# 1-stm32.net
KiCad netlist of a schematic drawn in Altium Designer
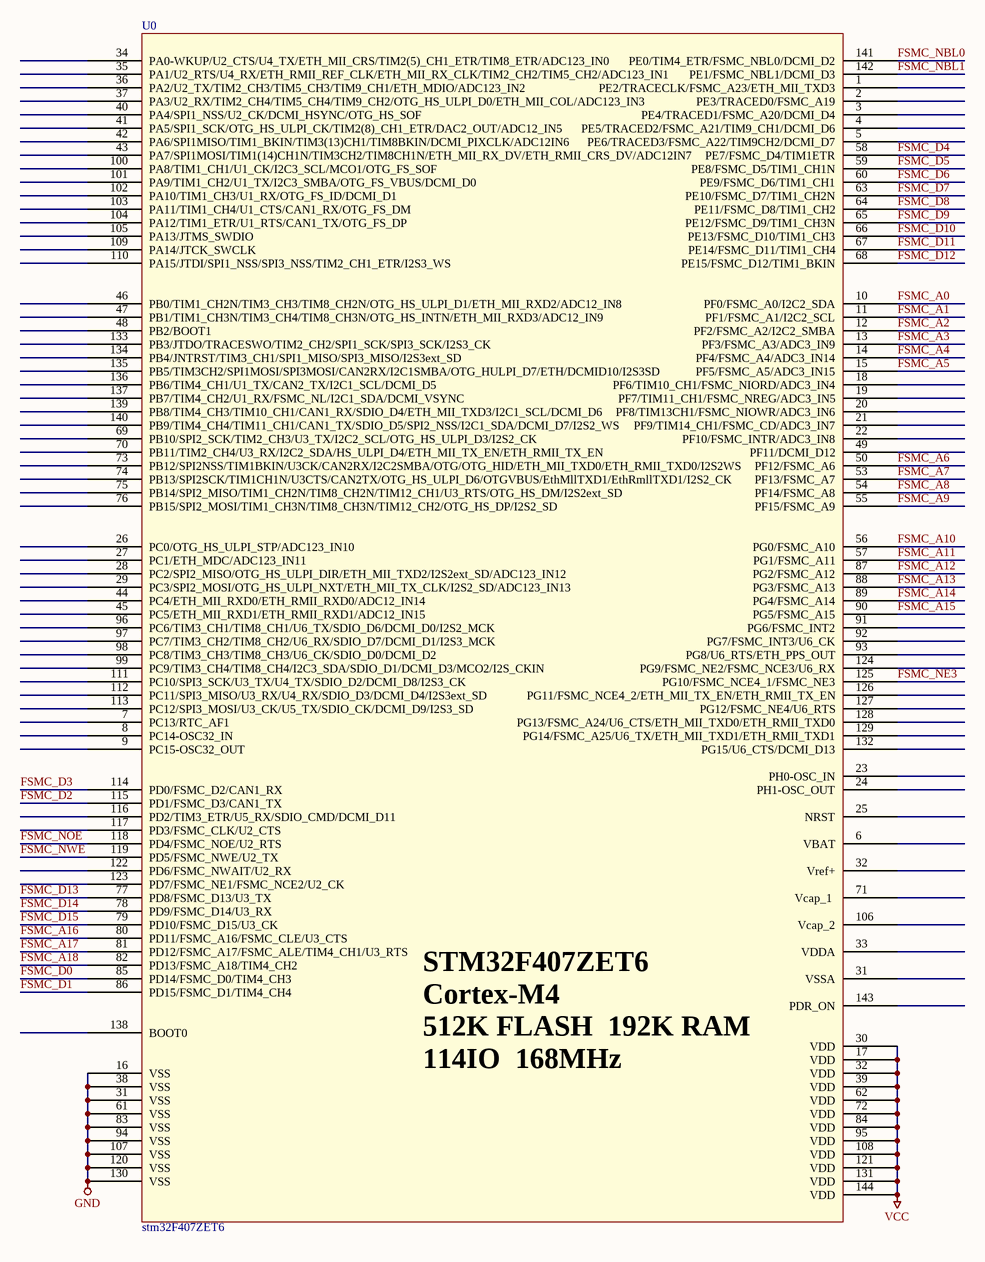
[diagram p0: 1-stm32.SchDoc]

(export (version "E")
  (design (tool "Eeschema 10.0.6"))
  (components
    (comp (ref "U0")
      (value "stm32F407ZET6")
      (footprint "STM-LQFP144_M")
      (libsource (lib "tianxiaohua_Schlib") (part "stm32F407ZET6"))
    )
  )
  (nets
    (net (code "1") (name "/FSMC_A0") (class "Default")
      (node (ref "U0") (pin "10") (pinfunction "PF0/FSMC_A0/I2C2_SDA_10") (pintype "passive"))
    )
    (net (code "2") (name "/FSMC_A1") (class "Default")
      (node (ref "U0") (pin "11") (pinfunction "PF1/FSMC_A1/I2C2_SCL_11") (pintype "passive"))
    )
    (net (code "3") (name "/FSMC_A2") (class "Default")
      (node (ref "U0") (pin "12") (pinfunction "PF2/FSMC_A2/I2C2_SMBA_12") (pintype "passive"))
    )
    (net (code "4") (name "/FSMC_A3") (class "Default")
      (node (ref "U0") (pin "13") (pinfunction "PF3/FSMC_A3/ADC3_IN9_13") (pintype "passive"))
    )
    (net (code "5") (name "/FSMC_A4") (class "Default")
      (node (ref "U0") (pin "14") (pinfunction "PF4/FSMC_A4/ADC3_IN14_14") (pintype "passive"))
    )
    (net (code "6") (name "/FSMC_A5") (class "Default")
      (node (ref "U0") (pin "15") (pinfunction "PF5/FSMC_A5/ADC3_IN15_15") (pintype "passive"))
    )
    (net (code "7") (name "/FSMC_A6") (class "Default")
      (node (ref "U0") (pin "50") (pinfunction "PF12/FSMC_A6_50") (pintype "passive"))
    )
    (net (code "8") (name "/FSMC_A7") (class "Default")
      (node (ref "U0") (pin "53") (pinfunction "PF13/FSMC_A7_53") (pintype "passive"))
    )
    (net (code "9") (name "/FSMC_A8") (class "Default")
      (node (ref "U0") (pin "54") (pinfunction "PF14/FSMC_A8_54") (pintype "passive"))
    )
    (net (code "10") (name "/FSMC_A9") (class "Default")
      (node (ref "U0") (pin "55") (pinfunction "PF15/FSMC_A9_55") (pintype "passive"))
    )
    (net (code "11") (name "/FSMC_A10") (class "Default")
      (node (ref "U0") (pin "56") (pinfunction "PG0/FSMC_A10_56") (pintype "passive"))
    )
    (net (code "12") (name "/FSMC_A11") (class "Default")
      (node (ref "U0") (pin "57") (pinfunction "PG1/FSMC_A11_57") (pintype "passive"))
    )
    (net (code "13") (name "/FSMC_A12") (class "Default")
      (node (ref "U0") (pin "87") (pinfunction "PG2/FSMC_A12_87") (pintype "passive"))
    )
    (net (code "14") (name "/FSMC_A13") (class "Default")
      (node (ref "U0") (pin "88") (pinfunction "PG3/FSMC_A13_88") (pintype "passive"))
    )
    (net (code "15") (name "/FSMC_A14") (class "Default")
      (node (ref "U0") (pin "89") (pinfunction "PG4/FSMC_A14_89") (pintype "passive"))
    )
    (net (code "16") (name "/FSMC_A15") (class "Default")
      (node (ref "U0") (pin "90") (pinfunction "PG5/FSMC_A15_90") (pintype "passive"))
    )
    (net (code "17") (name "/FSMC_A16") (class "Default")
      (node (ref "U0") (pin "80") (pinfunction "PD11/FSMC_A16/FSMC_CLE/U3_CTS_80") (pintype "passive"))
    )
    (net (code "18") (name "/FSMC_A17") (class "Default")
      (node (ref "U0") (pin "81") (pinfunction "PD12/FSMC_A17/FSMC_ALE/TIM4_CH1/U3_RTS_81") (pintype "passive"))
    )
    (net (code "19") (name "/FSMC_A18") (class "Default")
      (node (ref "U0") (pin "82") (pinfunction "PD13/FSMC_A18/TIM4_CH2_82") (pintype "passive"))
    )
    (net (code "20") (name "/FSMC_D0") (class "Default")
      (node (ref "U0") (pin "85") (pinfunction "PD14/FSMC_D0/TIM4_CH3_85") (pintype "passive"))
    )
    (net (code "21") (name "/FSMC_D1") (class "Default")
      (node (ref "U0") (pin "86") (pinfunction "PD15/FSMC_D1/TIM4_CH4_86") (pintype "passive"))
    )
    (net (code "22") (name "/FSMC_D2") (class "Default")
      (node (ref "U0") (pin "115") (pinfunction "PD1/FSMC_D3/CAN1_TX_115") (pintype "passive"))
    )
    (net (code "23") (name "/FSMC_D3") (class "Default")
      (node (ref "U0") (pin "114") (pinfunction "PD0/FSMC_D2/CAN1_RX_114") (pintype "passive"))
    )
    (net (code "24") (name "/FSMC_D4") (class "Default")
      (node (ref "U0") (pin "58") (pinfunction "PE7/FSMC_D4/TIM1ETR_58") (pintype "passive"))
    )
    (net (code "25") (name "/FSMC_D5") (class "Default")
      (node (ref "U0") (pin "59") (pinfunction "PE8/FSMC_D5/TIM1_CH1N_59") (pintype "passive"))
    )
    (net (code "26") (name "/FSMC_D6") (class "Default")
      (node (ref "U0") (pin "60") (pinfunction "PE9/FSMC_D6/TIM1_CH1_60") (pintype "passive"))
    )
    (net (code "27") (name "/FSMC_D7") (class "Default")
      (node (ref "U0") (pin "63") (pinfunction "PE10/FSMC_D7/TIM1_CH2N_63") (pintype "passive"))
    )
    (net (code "28") (name "/FSMC_D8") (class "Default")
      (node (ref "U0") (pin "64") (pinfunction "PE11/FSMC_D8/TIM1_CH2_64") (pintype "passive"))
    )
    (net (code "29") (name "/FSMC_D9") (class "Default")
      (node (ref "U0") (pin "65") (pinfunction "PE12/FSMC_D9/TIM1_CH3N_65") (pintype "passive"))
    )
    (net (code "30") (name "/FSMC_D10") (class "Default")
      (node (ref "U0") (pin "66") (pinfunction "PE13/FSMC_D10/TIM1_CH3_66") (pintype "passive"))
    )
    (net (code "31") (name "/FSMC_D11") (class "Default")
      (node (ref "U0") (pin "67") (pinfunction "PE14/FSMC_D11/TIM1_CH4_67") (pintype "passive"))
    )
    (net (code "32") (name "/FSMC_D12") (class "Default")
      (node (ref "U0") (pin "68") (pinfunction "PE15/FSMC_D12/TIM1_BKIN_68") (pintype "passive"))
    )
    (net (code "33") (name "/FSMC_D13") (class "Default")
      (node (ref "U0") (pin "77") (pinfunction "PD8/FSMC_D13/U3_TX_77") (pintype "passive"))
    )
    (net (code "34") (name "/FSMC_D14") (class "Default")
      (node (ref "U0") (pin "78") (pinfunction "PD9/FSMC_D14/U3_RX_78") (pintype "passive"))
    )
    (net (code "35") (name "/FSMC_D15") (class "Default")
      (node (ref "U0") (pin "79") (pinfunction "PD10/FSMC_D15/U3_CK_79") (pintype "passive"))
    )
    (net (code "36") (name "/FSMC_NBL0") (class "Default")
      (node (ref "U0") (pin "141") (pinfunction "PE0/TIM4_ETR/FSMC_NBL0/DCMI_D2_141") (pintype "passive"))
    )
    (net (code "37") (name "/FSMC_NBL1") (class "Default")
      (node (ref "U0") (pin "142") (pinfunction "PE1/FSMC_NBL1/DCMI_D3_142") (pintype "passive"))
    )
    (net (code "38") (name "/FSMC_NE3") (class "Default")
      (node (ref "U0") (pin "125") (pinfunction "PG10/FSMC_NCE4_1/FSMC_NE3_125") (pintype "passive"))
    )
    (net (code "39") (name "/FSMC_NOE") (class "Default")
      (node (ref "U0") (pin "118") (pinfunction "PD4/FSMC_NOE/U2_RTS_118") (pintype "passive"))
    )
    (net (code "40") (name "/FSMC_NWE") (class "Default")
      (node (ref "U0") (pin "119") (pinfunction "PD5/FSMC_NWE/U2_TX_119") (pintype "passive"))
    )
    (net (code "41") (name "GND") (class "Default")
      (node (ref "U0") (pin "107") (pinfunction "VSS_107") (pintype "passive"))
      (node (ref "U0") (pin "120") (pinfunction "VSS_120") (pintype "passive"))
      (node (ref "U0") (pin "130") (pinfunction "VSS_130") (pintype "passive"))
      (node (ref "U0") (pin "16") (pinfunction "VSS_16") (pintype "passive"))
      (node (ref "U0") (pin "31") (pinfunction "VSS_31") (pintype "passive"))
      (node (ref "U0") (pin "38") (pinfunction "VSS_38") (pintype "passive"))
      (node (ref "U0") (pin "61") (pinfunction "VSS_61") (pintype "passive"))
      (node (ref "U0") (pin "83") (pinfunction "VSS_83") (pintype "passive"))
      (node (ref "U0") (pin "94") (pinfunction "VSS_94") (pintype "passive"))
    )
    (net (code "42") (name "VCC") (class "Default")
      (node (ref "U0") (pin "108") (pinfunction "VDD_108") (pintype "passive"))
      (node (ref "U0") (pin "121") (pinfunction "VDD_121") (pintype "passive"))
      (node (ref "U0") (pin "131") (pinfunction "VDD_131") (pintype "passive"))
      (node (ref "U0") (pin "144") (pinfunction "VDD_144") (pintype "passive"))
      (node (ref "U0") (pin "17") (pinfunction "VDD_17") (pintype "passive"))
      (node (ref "U0") (pin "30") (pinfunction "VDD_30") (pintype "passive"))
      (node (ref "U0") (pin "32") (pinfunction "VDD_32") (pintype "passive"))
      (node (ref "U0") (pin "39") (pinfunction "VDD_39") (pintype "passive"))
      (node (ref "U0") (pin "62") (pinfunction "VDD_62") (pintype "passive"))
      (node (ref "U0") (pin "72") (pinfunction "VDD_72") (pintype "passive"))
      (node (ref "U0") (pin "84") (pinfunction "VDD_84") (pintype "passive"))
      (node (ref "U0") (pin "95") (pinfunction "VDD_95") (pintype "passive"))
    )
    (net (code "43") (name "unconnected-(U0-BOOT0-Pad138)") (class "Default")
      (node (ref "U0") (pin "138") (pinfunction "BOOT0_138") (pintype "passive"))
    )
    (net (code "44") (name "unconnected-(U0-NRST-Pad25)") (class "Default")
      (node (ref "U0") (pin "25") (pinfunction "NRST_25") (pintype "passive"))
    )
    (net (code "45") (name "unconnected-(U0-PA0-WKUP{slash}U2_CTS{slash}U4_TX{slash}ETH_MII_CRS{slash}TIM2(5)_CH1_ETR{slash}TIM8_ETR{slash}ADC123_IN0-Pad34)") (class "Default")
      (node (ref "U0") (pin "34") (pinfunction "PA0-WKUP/U2_CTS/U4_TX/ETH_MII_CRS/TIM2(5)_CH1_ETR/TIM8_ETR/ADC123_IN0_34") (pintype "passive"))
    )
    (net (code "46") (name "unconnected-(U0-PA1{slash}U2_RTS{slash}U4_RX{slash}ETH_RMII_REF_CLK{slash}ETH_MII_RX_CLK{slash}TIM2_CH2{slash}TIM5_CH2{slash}ADC123_IN1-Pad35)") (class "Default")
      (node (ref "U0") (pin "35") (pinfunction "PA1/U2_RTS/U4_RX/ETH_RMII_REF_CLK/ETH_MII_RX_CLK/TIM2_CH2/TIM5_CH2/ADC123_IN1_35") (pintype "passive"))
    )
    (net (code "47") (name "unconnected-(U0-PA2{slash}U2_TX{slash}TIM2_CH3{slash}TIM5_CH3{slash}TIM9_CH1{slash}ETH_MDIO{slash}ADC123_IN2-Pad36)") (class "Default")
      (node (ref "U0") (pin "36") (pinfunction "PA2/U2_TX/TIM2_CH3/TIM5_CH3/TIM9_CH1/ETH_MDIO/ADC123_IN2_36") (pintype "passive"))
    )
    (net (code "48") (name "unconnected-(U0-PA3{slash}U2_RX{slash}TIM2_CH4{slash}TIM5_CH4{slash}TIM9_CH2{slash}OTG_HS_ULPI_D0{slash}ETH_MII_COL{slash}ADC123_IN3-Pad37)") (class "Default")
      (node (ref "U0") (pin "37") (pinfunction "PA3/U2_RX/TIM2_CH4/TIM5_CH4/TIM9_CH2/OTG_HS_ULPI_D0/ETH_MII_COL/ADC123_IN3_37") (pintype "passive"))
    )
    (net (code "49") (name "unconnected-(U0-PA4{slash}SPI1_NSS{slash}U2_CK{slash}DCMI_HSYNC{slash}OTG_HS_SOF-Pad40)") (class "Default")
      (node (ref "U0") (pin "40") (pinfunction "PA4/SPI1_NSS/U2_CK/DCMI_HSYNC/OTG_HS_SOF_40") (pintype "passive"))
    )
    (net (code "50") (name "unconnected-(U0-PA5{slash}SPI1_SCK{slash}OTG_HS_ULPI_CK{slash}TIM2(8)_CH1_ETR{slash}DAC2_OUT{slash}ADC12_IN5-Pad41)") (class "Default")
      (node (ref "U0") (pin "41") (pinfunction "PA5/SPI1_SCK/OTG_HS_ULPI_CK/TIM2(8)_CH1_ETR/DAC2_OUT/ADC12_IN5_41") (pintype "passive"))
    )
    (net (code "51") (name "unconnected-(U0-PA6{slash}SPI1MISO{slash}TIM1_BKIN{slash}TIM3(13)CH1{slash}TIM8BKIN{slash}DCMI_PIXCLK{slash}ADC12IN6-Pad42)") (class "Default")
      (node (ref "U0") (pin "42") (pinfunction "PA6/SPI1MISO/TIM1_BKIN/TIM3(13)CH1/TIM8BKIN/DCMI_PIXCLK/ADC12IN6_42") (pintype "passive"))
    )
    (net (code "52") (name "unconnected-(U0-PA7{slash}SPI1MOSI{slash}TIM1(14)CH1N{slash}TIM3CH2{slash}TIM8CH1N{slash}ETH_MII_RX_DV{slash}ETH_RMII_CRS_DV{slash}ADC12IN7-Pad43)") (class "Default")
      (node (ref "U0") (pin "43") (pinfunction "PA7/SPI1MOSI/TIM1(14)CH1N/TIM3CH2/TIM8CH1N/ETH_MII_RX_DV/ETH_RMII_CRS_DV/ADC12IN7_43") (pintype "passive"))
    )
    (net (code "53") (name "unconnected-(U0-PA8{slash}TIM1_CH1{slash}U1_CK{slash}I2C3_SCL{slash}MCO1{slash}OTG_FS_SOF-Pad100)") (class "Default")
      (node (ref "U0") (pin "100") (pinfunction "PA8/TIM1_CH1/U1_CK/I2C3_SCL/MCO1/OTG_FS_SOF_100") (pintype "passive"))
    )
    (net (code "54") (name "unconnected-(U0-PA9{slash}TIM1_CH2{slash}U1_TX{slash}I2C3_SMBA{slash}OTG_FS_VBUS{slash}DCMI_D0-Pad101)") (class "Default")
      (node (ref "U0") (pin "101") (pinfunction "PA9/TIM1_CH2/U1_TX/I2C3_SMBA/OTG_FS_VBUS/DCMI_D0_101") (pintype "passive"))
    )
    (net (code "55") (name "unconnected-(U0-PA10{slash}TIM1_CH3{slash}U1_RX{slash}OTG_FS_ID{slash}DCMI_D1-Pad102)") (class "Default")
      (node (ref "U0") (pin "102") (pinfunction "PA10/TIM1_CH3/U1_RX/OTG_FS_ID/DCMI_D1_102") (pintype "passive"))
    )
    (net (code "56") (name "unconnected-(U0-PA11{slash}TIM1_CH4{slash}U1_CTS{slash}CAN1_RX{slash}OTG_FS_DM-Pad103)") (class "Default")
      (node (ref "U0") (pin "103") (pinfunction "PA11/TIM1_CH4/U1_CTS/CAN1_RX/OTG_FS_DM_103") (pintype "passive"))
    )
    (net (code "57") (name "unconnected-(U0-PA12{slash}TIM1_ETR{slash}U1_RTS{slash}CAN1_TX{slash}OTG_FS_DP-Pad104)") (class "Default")
      (node (ref "U0") (pin "104") (pinfunction "PA12/TIM1_ETR/U1_RTS/CAN1_TX/OTG_FS_DP_104") (pintype "passive"))
    )
    (net (code "58") (name "unconnected-(U0-PA13{slash}JTMS_SWDIO-Pad105)") (class "Default")
      (node (ref "U0") (pin "105") (pinfunction "PA13/JTMS_SWDIO_105") (pintype "passive"))
    )
    (net (code "59") (name "unconnected-(U0-PA14{slash}JTCK_SWCLK-Pad109)") (class "Default")
      (node (ref "U0") (pin "109") (pinfunction "PA14/JTCK_SWCLK_109") (pintype "passive"))
    )
    (net (code "60") (name "unconnected-(U0-PA15{slash}JTDI{slash}SPI1_NSS{slash}SPI3_NSS{slash}TIM2_CH1_ETR{slash}I2S3_WS-Pad110)") (class "Default")
      (node (ref "U0") (pin "110") (pinfunction "PA15/JTDI/SPI1_NSS/SPI3_NSS/TIM2_CH1_ETR/I2S3_WS_110") (pintype "passive"))
    )
    (net (code "61") (name "unconnected-(U0-PB0{slash}TIM1_CH2N{slash}TIM3_CH3{slash}TIM8_CH2N{slash}OTG_HS_ULPI_D1{slash}ETH_MII_RXD2{slash}ADC12_IN8-Pad46)") (class "Default")
      (node (ref "U0") (pin "46") (pinfunction "PB0/TIM1_CH2N/TIM3_CH3/TIM8_CH2N/OTG_HS_ULPI_D1/ETH_MII_RXD2/ADC12_IN8_46") (pintype "passive"))
    )
    (net (code "62") (name "unconnected-(U0-PB1{slash}TIM1_CH3N{slash}TIM3_CH4{slash}TIM8_CH3N{slash}OTG_HS_INTN{slash}ETH_MII_RXD3{slash}ADC12_IN9-Pad47)") (class "Default")
      (node (ref "U0") (pin "47") (pinfunction "PB1/TIM1_CH3N/TIM3_CH4/TIM8_CH3N/OTG_HS_INTN/ETH_MII_RXD3/ADC12_IN9_47") (pintype "passive"))
    )
    (net (code "63") (name "unconnected-(U0-PB2{slash}BOOT1-Pad48)") (class "Default")
      (node (ref "U0") (pin "48") (pinfunction "PB2/BOOT1_48") (pintype "passive"))
    )
    (net (code "64") (name "unconnected-(U0-PB3{slash}JTDO{slash}TRACESWO{slash}TIM2_CH2{slash}SPI1_SCK{slash}SPI3_SCK{slash}I2S3_CK-Pad133)") (class "Default")
      (node (ref "U0") (pin "133") (pinfunction "PB3/JTDO/TRACESWO/TIM2_CH2/SPI1_SCK/SPI3_SCK/I2S3_CK_133") (pintype "passive"))
    )
    (net (code "65") (name "unconnected-(U0-PB4{slash}JNTRST{slash}TIM3_CH1{slash}SPI1_MISO{slash}SPI3_MISO{slash}I2S3ext_SD-Pad134)") (class "Default")
      (node (ref "U0") (pin "134") (pinfunction "PB4/JNTRST/TIM3_CH1/SPI1_MISO/SPI3_MISO/I2S3ext_SD_134") (pintype "passive"))
    )
    (net (code "66") (name "unconnected-(U0-PB5{slash}TIM3CH2{slash}SPI1MOSI{slash}SPI3MOSI{slash}CAN2RX{slash}I2C1SMBA{slash}OTG_HULPI_D7{slash}ETH{slash}DCMID10{slash}I2S3SD-Pad135)") (class "Default")
      (node (ref "U0") (pin "135") (pinfunction "PB5/TIM3CH2/SPI1MOSI/SPI3MOSI/CAN2RX/I2C1SMBA/OTG_HULPI_D7/ETH/DCMID10/I2S3SD_135") (pintype "passive"))
    )
    (net (code "67") (name "unconnected-(U0-PB6{slash}TIM4_CH1{slash}U1_TX{slash}CAN2_TX{slash}I2C1_SCL{slash}DCMI_D5-Pad136)") (class "Default")
      (node (ref "U0") (pin "136") (pinfunction "PB6/TIM4_CH1/U1_TX/CAN2_TX/I2C1_SCL/DCMI_D5_136") (pintype "passive"))
    )
    (net (code "68") (name "unconnected-(U0-PB7{slash}TIM4_CH2{slash}U1_RX{slash}FSMC_NL{slash}I2C1_SDA{slash}DCMI_VSYNC-Pad137)") (class "Default")
      (node (ref "U0") (pin "137") (pinfunction "PB7/TIM4_CH2/U1_RX/FSMC_NL/I2C1_SDA/DCMI_VSYNC_137") (pintype "passive"))
    )
    (net (code "69") (name "unconnected-(U0-PB8{slash}TIM4_CH3{slash}TIM10_CH1{slash}CAN1_RX{slash}SDIO_D4{slash}ETH_MII_TXD3{slash}I2C1_SCL{slash}DCMI_D6-Pad139)") (class "Default")
      (node (ref "U0") (pin "139") (pinfunction "PB8/TIM4_CH3/TIM10_CH1/CAN1_RX/SDIO_D4/ETH_MII_TXD3/I2C1_SCL/DCMI_D6_139") (pintype "passive"))
    )
    (net (code "70") (name "unconnected-(U0-PB9{slash}TIM4_CH4{slash}TIM11_CH1{slash}CAN1_TX{slash}SDIO_D5{slash}SPI2_NSS{slash}I2C1_SDA{slash}DCMI_D7{slash}I2S2_WS-Pad140)") (class "Default")
      (node (ref "U0") (pin "140") (pinfunction "PB9/TIM4_CH4/TIM11_CH1/CAN1_TX/SDIO_D5/SPI2_NSS/I2C1_SDA/DCMI_D7/I2S2_WS_140") (pintype "passive"))
    )
    (net (code "71") (name "unconnected-(U0-PB10{slash}SPI2_SCK{slash}TIM2_CH3{slash}U3_TX{slash}I2C2_SCL{slash}OTG_HS_ULPI_D3{slash}I2S2_CK-Pad69)") (class "Default")
      (node (ref "U0") (pin "69") (pinfunction "PB10/SPI2_SCK/TIM2_CH3/U3_TX/I2C2_SCL/OTG_HS_ULPI_D3/I2S2_CK_69") (pintype "passive"))
    )
    (net (code "72") (name "unconnected-(U0-PB11{slash}TIM2_CH4{slash}U3_RX{slash}I2C2_SDA{slash}HS_ULPI_D4{slash}ETH_MII_TX_EN{slash}ETH_RMII_TX_EN-Pad70)") (class "Default")
      (node (ref "U0") (pin "70") (pinfunction "PB11/TIM2_CH4/U3_RX/I2C2_SDA/HS_ULPI_D4/ETH_MII_TX_EN/ETH_RMII_TX_EN_70") (pintype "passive"))
    )
    (net (code "73") (name "unconnected-(U0-PB12{slash}SPI2NSS{slash}TIM1BKIN{slash}U3CK{slash}CAN2RX{slash}I2C2SMBA{slash}OTG{slash}OTG_HID{slash}ETH_MII_TXD0{slash}ETH_RMII_TXD0{slash}I2S2WS-Pad73)") (class "Default")
      (node (ref "U0") (pin "73") (pinfunction "PB12/SPI2NSS/TIM1BKIN/U3CK/CAN2RX/I2C2SMBA/OTG/OTG_HID/ETH_MII_TXD0/ETH_RMII_TXD0/I2S2WS_73") (pintype "passive"))
    )
    (net (code "74") (name "unconnected-(U0-PB13{slash}SPI2SCK{slash}TIM1CH1N{slash}U3CTS{slash}CAN2TX{slash}OTG_HS_ULPI_D6{slash}OTGVBUS{slash}EthMllTXD1{slash}EthRmllTXD1{slash}I2S2_CK-Pad74)") (class "Default")
      (node (ref "U0") (pin "74") (pinfunction "PB13/SPI2SCK/TIM1CH1N/U3CTS/CAN2TX/OTG_HS_ULPI_D6/OTGVBUS/EthMllTXD1/EthRmllTXD1/I2S2_CK_74") (pintype "passive"))
    )
    (net (code "75") (name "unconnected-(U0-PB14{slash}SPI2_MISO{slash}TIM1_CH2N{slash}TIM8_CH2N{slash}TIM12_CH1{slash}U3_RTS{slash}OTG_HS_DM{slash}I2S2ext_SD-Pad75)") (class "Default")
      (node (ref "U0") (pin "75") (pinfunction "PB14/SPI2_MISO/TIM1_CH2N/TIM8_CH2N/TIM12_CH1/U3_RTS/OTG_HS_DM/I2S2ext_SD_75") (pintype "passive"))
    )
    (net (code "76") (name "unconnected-(U0-PB15{slash}SPI2_MOSI{slash}TIM1_CH3N{slash}TIM8_CH3N{slash}TIM12_CH2{slash}OTG_HS_DP{slash}I2S2_SD-Pad76)") (class "Default")
      (node (ref "U0") (pin "76") (pinfunction "PB15/SPI2_MOSI/TIM1_CH3N/TIM8_CH3N/TIM12_CH2/OTG_HS_DP/I2S2_SD_76") (pintype "passive"))
    )
    (net (code "77") (name "unconnected-(U0-PC0{slash}OTG_HS_ULPI_STP{slash}ADC123_IN10-Pad26)") (class "Default")
      (node (ref "U0") (pin "26") (pinfunction "PC0/OTG_HS_ULPI_STP/ADC123_IN10_26") (pintype "passive"))
    )
    (net (code "78") (name "unconnected-(U0-PC1{slash}ETH_MDC{slash}ADC123_IN11-Pad27)") (class "Default")
      (node (ref "U0") (pin "27") (pinfunction "PC1/ETH_MDC/ADC123_IN11_27") (pintype "passive"))
    )
    (net (code "79") (name "unconnected-(U0-PC2{slash}SPI2_MISO{slash}OTG_HS_ULPI_DIR{slash}ETH_MII_TXD2{slash}I2S2ext_SD{slash}ADC123_IN12-Pad28)") (class "Default")
      (node (ref "U0") (pin "28") (pinfunction "PC2/SPI2_MISO/OTG_HS_ULPI_DIR/ETH_MII_TXD2/I2S2ext_SD/ADC123_IN12_28") (pintype "passive"))
    )
    (net (code "80") (name "unconnected-(U0-PC3{slash}SPI2_MOSI{slash}OTG_HS_ULPI_NXT{slash}ETH_MII_TX_CLK{slash}I2S2_SD{slash}ADC123_IN13-Pad29)") (class "Default")
      (node (ref "U0") (pin "29") (pinfunction "PC3/SPI2_MOSI/OTG_HS_ULPI_NXT/ETH_MII_TX_CLK/I2S2_SD/ADC123_IN13_29") (pintype "passive"))
    )
    (net (code "81") (name "unconnected-(U0-PC4{slash}ETH_MII_RXD0{slash}ETH_RMII_RXD0{slash}ADC12_IN14-Pad44)") (class "Default")
      (node (ref "U0") (pin "44") (pinfunction "PC4/ETH_MII_RXD0/ETH_RMII_RXD0/ADC12_IN14_44") (pintype "passive"))
    )
    (net (code "82") (name "unconnected-(U0-PC5{slash}ETH_MII_RXD1{slash}ETH_RMII_RXD1{slash}ADC12_IN15-Pad45)") (class "Default")
      (node (ref "U0") (pin "45") (pinfunction "PC5/ETH_MII_RXD1/ETH_RMII_RXD1/ADC12_IN15_45") (pintype "passive"))
    )
    (net (code "83") (name "unconnected-(U0-PC6{slash}TIM3_CH1{slash}TIM8_CH1{slash}U6_TX{slash}SDIO_D6{slash}DCMI_D0{slash}I2S2_MCK-Pad96)") (class "Default")
      (node (ref "U0") (pin "96") (pinfunction "PC6/TIM3_CH1/TIM8_CH1/U6_TX/SDIO_D6/DCMI_D0/I2S2_MCK_96") (pintype "passive"))
    )
    (net (code "84") (name "unconnected-(U0-PC7{slash}TIM3_CH2{slash}TIM8_CH2{slash}U6_RX{slash}SDIO_D7{slash}DCMI_D1{slash}I2S3_MCK-Pad97)") (class "Default")
      (node (ref "U0") (pin "97") (pinfunction "PC7/TIM3_CH2/TIM8_CH2/U6_RX/SDIO_D7/DCMI_D1/I2S3_MCK_97") (pintype "passive"))
    )
    (net (code "85") (name "unconnected-(U0-PC8{slash}TIM3_CH3{slash}TIM8_CH3{slash}U6_CK{slash}SDIO_D0{slash}DCMI_D2-Pad98)") (class "Default")
      (node (ref "U0") (pin "98") (pinfunction "PC8/TIM3_CH3/TIM8_CH3/U6_CK/SDIO_D0/DCMI_D2_98") (pintype "passive"))
    )
    (net (code "86") (name "unconnected-(U0-PC9{slash}TIM3_CH4{slash}TIM8_CH4{slash}I2C3_SDA{slash}SDIO_D1{slash}DCMI_D3{slash}MCO2{slash}I2S_CKIN-Pad99)") (class "Default")
      (node (ref "U0") (pin "99") (pinfunction "PC9/TIM3_CH4/TIM8_CH4/I2C3_SDA/SDIO_D1/DCMI_D3/MCO2/I2S_CKIN_99") (pintype "passive"))
    )
    (net (code "87") (name "unconnected-(U0-PC10{slash}SPI3_SCK{slash}U3_TX{slash}U4_TX{slash}SDIO_D2{slash}DCMI_D8{slash}I2S3_CK-Pad111)") (class "Default")
      (node (ref "U0") (pin "111") (pinfunction "PC10/SPI3_SCK/U3_TX/U4_TX/SDIO_D2/DCMI_D8/I2S3_CK_111") (pintype "passive"))
    )
    (net (code "88") (name "unconnected-(U0-PC11{slash}SPI3_MISO{slash}U3_RX{slash}U4_RX{slash}SDIO_D3{slash}DCMI_D4{slash}I2S3ext_SD-Pad112)") (class "Default")
      (node (ref "U0") (pin "112") (pinfunction "PC11/SPI3_MISO/U3_RX/U4_RX/SDIO_D3/DCMI_D4/I2S3ext_SD_112") (pintype "passive"))
    )
    (net (code "89") (name "unconnected-(U0-PC12{slash}SPI3_MOSI{slash}U3_CK{slash}U5_TX{slash}SDIO_CK{slash}DCMI_D9{slash}I2S3_SD-Pad113)") (class "Default")
      (node (ref "U0") (pin "113") (pinfunction "PC12/SPI3_MOSI/U3_CK/U5_TX/SDIO_CK/DCMI_D9/I2S3_SD_113") (pintype "passive"))
    )
    (net (code "90") (name "unconnected-(U0-PC13{slash}RTC_AF1-Pad7)") (class "Default")
      (node (ref "U0") (pin "7") (pinfunction "PC13/RTC_AF1_7") (pintype "passive"))
    )
    (net (code "91") (name "unconnected-(U0-PC14-OSC32_IN-Pad8)") (class "Default")
      (node (ref "U0") (pin "8") (pinfunction "PC14-OSC32_IN_8") (pintype "passive"))
    )
    (net (code "92") (name "unconnected-(U0-PC15-OSC32_OUT-Pad9)") (class "Default")
      (node (ref "U0") (pin "9") (pinfunction "PC15-OSC32_OUT_9") (pintype "passive"))
    )
    (net (code "93") (name "unconnected-(U0-PD2{slash}TIM3_ETR{slash}U5_RX{slash}SDIO_CMD{slash}DCMI_D11-Pad116)") (class "Default")
      (node (ref "U0") (pin "116") (pinfunction "PD2/TIM3_ETR/U5_RX/SDIO_CMD/DCMI_D11_116") (pintype "passive"))
    )
    (net (code "94") (name "unconnected-(U0-PD3{slash}FSMC_CLK{slash}U2_CTS-Pad117)") (class "Default")
      (node (ref "U0") (pin "117") (pinfunction "PD3/FSMC_CLK/U2_CTS_117") (pintype "passive"))
    )
    (net (code "95") (name "unconnected-(U0-PD6{slash}FSMC_NWAIT{slash}U2_RX-Pad122)") (class "Default")
      (node (ref "U0") (pin "122") (pinfunction "PD6/FSMC_NWAIT/U2_RX_122") (pintype "passive"))
    )
    (net (code "96") (name "unconnected-(U0-PD7{slash}FSMC_NE1{slash}FSMC_NCE2{slash}U2_CK-Pad123)") (class "Default")
      (node (ref "U0") (pin "123") (pinfunction "PD7/FSMC_NE1/FSMC_NCE2/U2_CK_123") (pintype "passive"))
    )
    (net (code "97") (name "unconnected-(U0-PDR_ON-Pad143)") (class "Default")
      (node (ref "U0") (pin "143") (pinfunction "PDR_ON_143") (pintype "passive"))
    )
    (net (code "98") (name "unconnected-(U0-PE2{slash}TRACECLK{slash}FSMC_A23{slash}ETH_MII_TXD3-Pad1)") (class "Default")
      (node (ref "U0") (pin "1") (pinfunction "PE2/TRACECLK/FSMC_A23/ETH_MII_TXD3_1") (pintype "passive"))
    )
    (net (code "99") (name "unconnected-(U0-PE3{slash}TRACED0{slash}FSMC_A19-Pad2)") (class "Default")
      (node (ref "U0") (pin "2") (pinfunction "PE3/TRACED0/FSMC_A19_2") (pintype "passive"))
    )
    (net (code "100") (name "unconnected-(U0-PE4{slash}TRACED1{slash}FSMC_A20{slash}DCMI_D4-Pad3)") (class "Default")
      (node (ref "U0") (pin "3") (pinfunction "PE4/TRACED1/FSMC_A20/DCMI_D4_3") (pintype "passive"))
    )
    (net (code "101") (name "unconnected-(U0-PE5{slash}TRACED2{slash}FSMC_A21{slash}TIM9_CH1{slash}DCMI_D6-Pad4)") (class "Default")
      (node (ref "U0") (pin "4") (pinfunction "PE5/TRACED2/FSMC_A21/TIM9_CH1/DCMI_D6_4") (pintype "passive"))
    )
    (net (code "102") (name "unconnected-(U0-PE6{slash}TRACED3{slash}FSMC_A22{slash}TIM9CH2{slash}DCMI_D7-Pad5)") (class "Default")
      (node (ref "U0") (pin "5") (pinfunction "PE6/TRACED3/FSMC_A22/TIM9CH2/DCMI_D7_5") (pintype "passive"))
    )
    (net (code "103") (name "unconnected-(U0-PF6{slash}TIM10_CH1{slash}FSMC_NIORD{slash}ADC3_IN4-Pad18)") (class "Default")
      (node (ref "U0") (pin "18") (pinfunction "PF6/TIM10_CH1/FSMC_NIORD/ADC3_IN4_18") (pintype "passive"))
    )
    (net (code "104") (name "unconnected-(U0-PF7{slash}TIM11_CH1{slash}FSMC_NREG{slash}ADC3_IN5-Pad19)") (class "Default")
      (node (ref "U0") (pin "19") (pinfunction "PF7/TIM11_CH1/FSMC_NREG/ADC3_IN5_19") (pintype "passive"))
    )
    (net (code "105") (name "unconnected-(U0-PF8{slash}TIM13CH1{slash}FSMC_NIOWR{slash}ADC3_IN6-Pad20)") (class "Default")
      (node (ref "U0") (pin "20") (pinfunction "PF8/TIM13CH1/FSMC_NIOWR/ADC3_IN6_20") (pintype "passive"))
    )
    (net (code "106") (name "unconnected-(U0-PF9{slash}TIM14_CH1{slash}FSMC_CD{slash}ADC3_IN7-Pad21)") (class "Default")
      (node (ref "U0") (pin "21") (pinfunction "PF9/TIM14_CH1/FSMC_CD/ADC3_IN7_21") (pintype "passive"))
    )
    (net (code "107") (name "unconnected-(U0-PF10{slash}FSMC_INTR{slash}ADC3_IN8-Pad22)") (class "Default")
      (node (ref "U0") (pin "22") (pinfunction "PF10/FSMC_INTR/ADC3_IN8_22") (pintype "passive"))
    )
    (net (code "108") (name "unconnected-(U0-PF11{slash}DCMI_D12-Pad49)") (class "Default")
      (node (ref "U0") (pin "49") (pinfunction "PF11/DCMI_D12_49") (pintype "passive"))
    )
    (net (code "109") (name "unconnected-(U0-PG6{slash}FSMC_INT2-Pad91)") (class "Default")
      (node (ref "U0") (pin "91") (pinfunction "PG6/FSMC_INT2_91") (pintype "passive"))
    )
    (net (code "110") (name "unconnected-(U0-PG7{slash}FSMC_INT3{slash}U6_CK-Pad92)") (class "Default")
      (node (ref "U0") (pin "92") (pinfunction "PG7/FSMC_INT3/U6_CK_92") (pintype "passive"))
    )
    (net (code "111") (name "unconnected-(U0-PG8{slash}U6_RTS{slash}ETH_PPS_OUT-Pad93)") (class "Default")
      (node (ref "U0") (pin "93") (pinfunction "PG8/U6_RTS/ETH_PPS_OUT_93") (pintype "passive"))
    )
    (net (code "112") (name "unconnected-(U0-PG9{slash}FSMC_NE2{slash}FSMC_NCE3{slash}U6_RX-Pad124)") (class "Default")
      (node (ref "U0") (pin "124") (pinfunction "PG9/FSMC_NE2/FSMC_NCE3/U6_RX_124") (pintype "passive"))
    )
    (net (code "113") (name "unconnected-(U0-PG11{slash}FSMC_NCE4_2{slash}ETH_MII_TX_EN{slash}ETH_RMII_TX_EN-Pad126)") (class "Default")
      (node (ref "U0") (pin "126") (pinfunction "PG11/FSMC_NCE4_2/ETH_MII_TX_EN/ETH_RMII_TX_EN_126") (pintype "passive"))
    )
    (net (code "114") (name "unconnected-(U0-PG12{slash}FSMC_NE4{slash}U6_RTS-Pad127)") (class "Default")
      (node (ref "U0") (pin "127") (pinfunction "PG12/FSMC_NE4/U6_RTS_127") (pintype "passive"))
    )
    (net (code "115") (name "unconnected-(U0-PG13{slash}FSMC_A24{slash}U6_CTS{slash}ETH_MII_TXD0{slash}ETH_RMII_TXD0-Pad128)") (class "Default")
      (node (ref "U0") (pin "128") (pinfunction "PG13/FSMC_A24/U6_CTS/ETH_MII_TXD0/ETH_RMII_TXD0_128") (pintype "passive"))
    )
    (net (code "116") (name "unconnected-(U0-PG14{slash}FSMC_A25{slash}U6_TX{slash}ETH_MII_TXD1{slash}ETH_RMII_TXD1-Pad129)") (class "Default")
      (node (ref "U0") (pin "129") (pinfunction "PG14/FSMC_A25/U6_TX/ETH_MII_TXD1/ETH_RMII_TXD1_129") (pintype "passive"))
    )
    (net (code "117") (name "unconnected-(U0-PG15{slash}U6_CTS{slash}DCMI_D13-Pad132)") (class "Default")
      (node (ref "U0") (pin "132") (pinfunction "PG15/U6_CTS/DCMI_D13_132") (pintype "passive"))
    )
    (net (code "118") (name "unconnected-(U0-PH0-OSC_IN-Pad23)") (class "Default")
      (node (ref "U0") (pin "23") (pinfunction "PH0-OSC_IN_23") (pintype "passive"))
    )
    (net (code "119") (name "unconnected-(U0-PH1-OSC_OUT-Pad24)") (class "Default")
      (node (ref "U0") (pin "24") (pinfunction "PH1-OSC_OUT_24") (pintype "passive"))
    )
    (net (code "120") (name "unconnected-(U0-VBAT-Pad6)") (class "Default")
      (node (ref "U0") (pin "6") (pinfunction "VBAT_6") (pintype "passive"))
    )
    (net (code "121") (name "unconnected-(U0-VDDA-Pad33)") (class "Default")
      (node (ref "U0") (pin "33") (pinfunction "VDDA_33") (pintype "passive"))
    )
    (net (code "122") (name "unconnected-(U0-VSSA-Pad31)") (class "Default")
      (node (ref "U0") (pin "31") (pinfunction "VSSA_31") (pintype "passive"))
    )
    (net (code "123") (name "unconnected-(U0-Vcap_1-Pad71)") (class "Default")
      (node (ref "U0") (pin "71") (pinfunction "Vcap_1_71") (pintype "passive"))
    )
    (net (code "124") (name "unconnected-(U0-Vcap_2-Pad106)") (class "Default")
      (node (ref "U0") (pin "106") (pinfunction "Vcap_2_106") (pintype "passive"))
    )
    (net (code "125") (name "unconnected-(U0-Vref+-Pad32)") (class "Default")
      (node (ref "U0") (pin "32") (pinfunction "Vref+_32") (pintype "passive"))
    )
  )
)
